# AS5047.net
KiCad netlist of a schematic drawn in Altium Designer
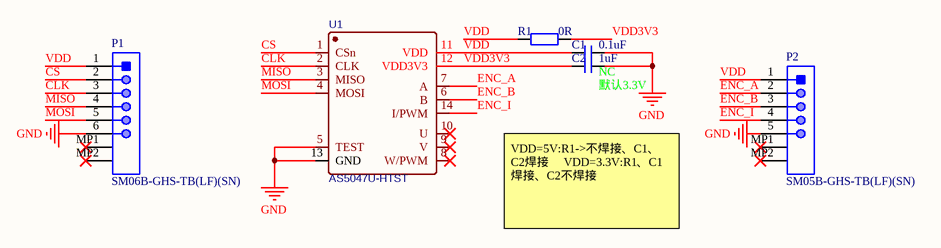
[diagram p0: AS5047.SchDoc]

(export (version "E")
  (design (tool "Eeschema 10.0.6"))
  (components
    (comp (ref "C1")
      (value "0.1uF")
      (footprint "C 0603_L")
      (description "贴片电容")
      (libsource (lib "0.1 - 电阻-电容-电感") (part "C"))
    )
    (comp (ref "C2")
      (value "1uF")
      (footprint "C 0603_L")
      (description "贴片电容")
      (libsource (lib "0.1 - 电阻-电容-电感") (part "C"))
    )
    (comp (ref "P1")
      (value "SM06B-GHS-TB(LF)(SN)")
      (footprint "JST-SM06B-GHS-TB_V")
      (fields (field (name "MANUFACTURER") "JST"))
      (libsource (lib "JST GH connector") (part "SM06B-GHS-TB(LF)(SN)"))
    )
    (comp (ref "P2")
      (value "SM05B-GHS-TB(LF)(SN)")
      (footprint "JST-SM05B-GHS-TB_V")
      (fields (field (name "MANUFACTURER") "JST"))
      (libsource (lib "JST GH connector") (part "SM05B-GHS-TB(LF)(SN)"))
    )
    (comp (ref "R1")
      (value "0R")
      (footprint "R 0603_L")
      (description "贴片电阻")
      (libsource (lib "0.1 - 电阻-电容-电感") (part "R"))
    )
    (comp (ref "U1")
      (value "AS5047U-HTST")
      (footprint "TSSOP-14_L5.0-W4.4-P0.65-LS6.4-BL")
      (fields (field (name "BOM_SUPPLIER PART") "C2153660") (field (name "CONTRIBUTOR") "LCSC"))
      (libsource (lib "mx_pcb_library") (part "AS5047U-HTST"))
    )
  )
  (nets
    (net (code "1") (name "/CLK") (class "Default")
      (node (ref "P1") (pin "3") (pinfunction "3_3") (pintype "passive"))
      (node (ref "U1") (pin "2") (pinfunction "CLK_2") (pintype "passive"))
    )
    (net (code "2") (name "/CS") (class "Default")
      (node (ref "P1") (pin "2") (pinfunction "2_2") (pintype "passive"))
      (node (ref "U1") (pin "1") (pinfunction "CSn_1") (pintype "passive"))
    )
    (net (code "3") (name "/ENC_A") (class "Default")
      (node (ref "P2") (pin "2") (pinfunction "2_2") (pintype "passive"))
      (node (ref "U1") (pin "7") (pinfunction "A_7") (pintype "passive"))
    )
    (net (code "4") (name "/ENC_B") (class "Default")
      (node (ref "P2") (pin "3") (pinfunction "3_3") (pintype "passive"))
      (node (ref "U1") (pin "6") (pinfunction "B_6") (pintype "passive"))
    )
    (net (code "5") (name "/ENC_I") (class "Default")
      (node (ref "P2") (pin "4") (pinfunction "4_4") (pintype "passive"))
      (node (ref "U1") (pin "14") (pinfunction "I/PWM_14") (pintype "passive"))
    )
    (net (code "6") (name "/MISO") (class "Default")
      (node (ref "P1") (pin "4") (pinfunction "4_4") (pintype "passive"))
      (node (ref "U1") (pin "3") (pinfunction "MISO_3") (pintype "passive"))
    )
    (net (code "7") (name "/MOSI") (class "Default")
      (node (ref "P1") (pin "5") (pinfunction "5_5") (pintype "passive"))
      (node (ref "U1") (pin "4") (pinfunction "MOSI_4") (pintype "passive"))
    )
    (net (code "8") (name "/VDD") (class "Default")
      (node (ref "C1") (pin "1") (pinfunction "1_1") (pintype "passive"))
      (node (ref "P1") (pin "1") (pinfunction "1_1") (pintype "passive"))
      (node (ref "P2") (pin "1") (pinfunction "1_1") (pintype "passive"))
      (node (ref "R1") (pin "1") (pinfunction "1_1") (pintype "passive"))
      (node (ref "U1") (pin "11") (pinfunction "VDD_11") (pintype "passive"))
    )
    (net (code "9") (name "/VDD3V3") (class "Default")
      (node (ref "C2") (pin "1") (pinfunction "1_1") (pintype "passive"))
      (node (ref "R1") (pin "2") (pinfunction "2_2") (pintype "passive"))
      (node (ref "U1") (pin "12") (pinfunction "VDD3V3_12") (pintype "passive"))
    )
    (net (code "10") (name "GND") (class "Default")
      (node (ref "C1") (pin "2") (pinfunction "2_2") (pintype "passive"))
      (node (ref "C2") (pin "2") (pinfunction "2_2") (pintype "passive"))
      (node (ref "P1") (pin "6") (pinfunction "6_6") (pintype "passive"))
      (node (ref "P2") (pin "5") (pinfunction "5_5") (pintype "passive"))
      (node (ref "U1") (pin "13") (pinfunction "GND_13") (pintype "passive"))
      (node (ref "U1") (pin "5") (pinfunction "TEST_5") (pintype "passive"))
    )
    (net (code "11") (name "unconnected-(P1-PadMP1)") (class "Default")
      (node (ref "P1") (pin "MP1") (pinfunction "MP1_MP1") (pintype "passive+no_connect"))
    )
    (net (code "12") (name "unconnected-(P1-PadMP2)") (class "Default")
      (node (ref "P1") (pin "MP2") (pinfunction "MP2_MP2") (pintype "passive+no_connect"))
    )
    (net (code "13") (name "unconnected-(P2-PadMP1)") (class "Default")
      (node (ref "P2") (pin "MP1") (pinfunction "MP1_MP1") (pintype "passive+no_connect"))
    )
    (net (code "14") (name "unconnected-(P2-PadMP2)") (class "Default")
      (node (ref "P2") (pin "MP2") (pinfunction "MP2_MP2") (pintype "passive+no_connect"))
    )
    (net (code "15") (name "unconnected-(U1-U-Pad10)") (class "Default")
      (node (ref "U1") (pin "10") (pinfunction "U_10") (pintype "passive+no_connect"))
    )
    (net (code "16") (name "unconnected-(U1-V-Pad9)") (class "Default")
      (node (ref "U1") (pin "9") (pinfunction "V_9") (pintype "passive+no_connect"))
    )
    (net (code "17") (name "unconnected-(U1-W{slash}PWM-Pad8)") (class "Default")
      (node (ref "U1") (pin "8") (pinfunction "W/PWM_8") (pintype "passive+no_connect"))
    )
  )
)
